# MasterBetaKit-v2-simple.net
KiCad netlist of a schematic drawn in EAGLE
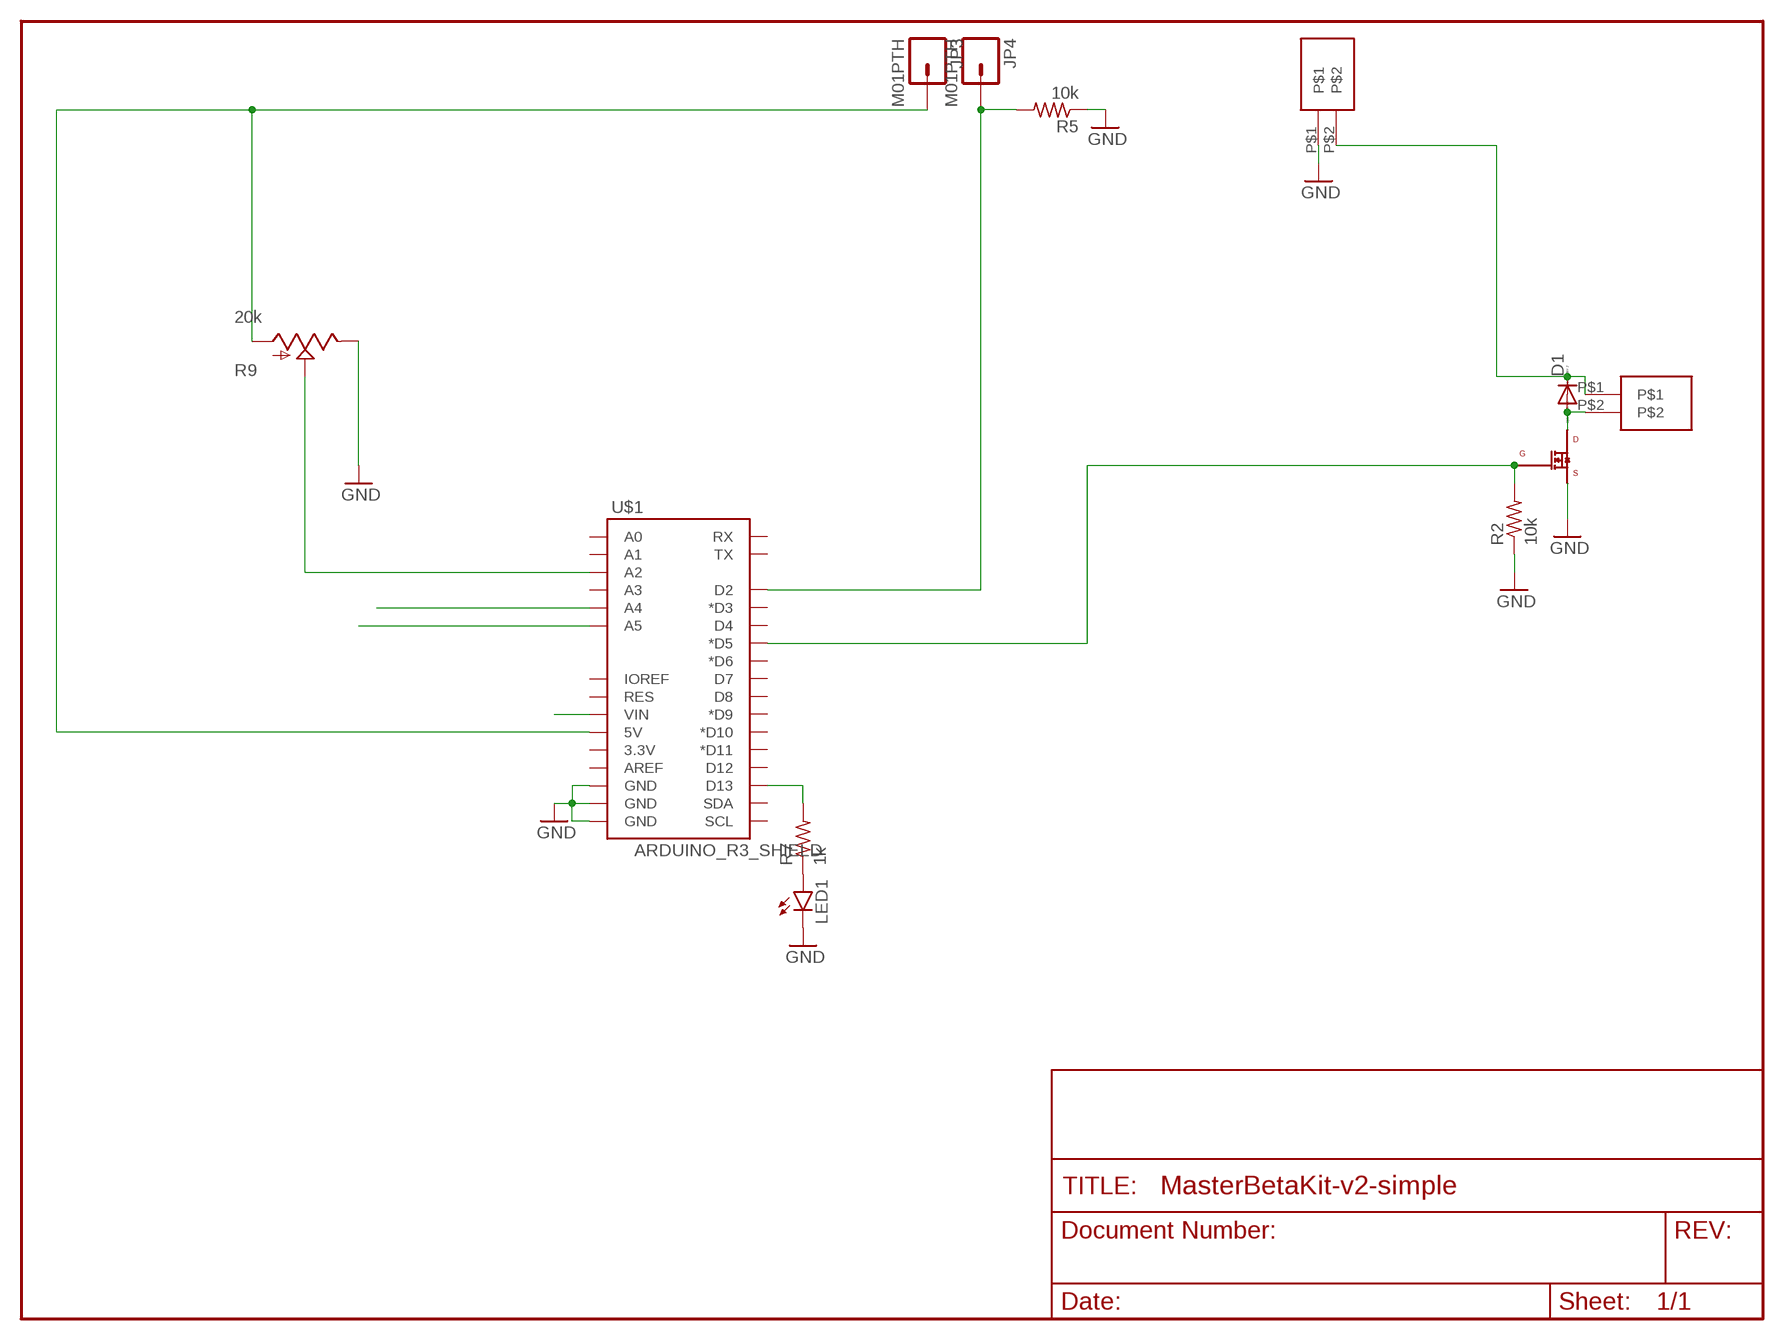
[diagram p0: schematic, sheet 1]

(export (version "E")
  (design (tool "Eeschema 10.0.6"))
  (components
    (comp (ref "D1")
      (value "DIODE-DO-214AC")
      (footprint "eagle-import:DO-214AC")
      (libsource (lib "eagle-import") (part "DIODE-DO-214AC"))
    )
    (comp (ref "JP3")
      (value "M01PTH")
      (footprint "eagle-import:1X01")
      (libsource (lib "eagle-import") (part "M01PTH"))
    )
    (comp (ref "JP4")
      (value "M01PTH")
      (footprint "eagle-import:1X01")
      (libsource (lib "eagle-import") (part "M01PTH"))
    )
    (comp (ref "LED1")
      (value "LED-3MM-NO_SILK")
      (footprint "eagle-import:LED3MM-NS")
      (libsource (lib "eagle-import") (part "LED-3MM-NO_SILK"))
    )
    (comp (ref "R2")
      (value "10k")
      (footprint "eagle-import:R0603")
      (libsource (lib "eagle-import") (part "R-US_R0603"))
    )
    (comp (ref "R5")
      (value "10k")
      (footprint "eagle-import:R0603")
      (libsource (lib "eagle-import") (part "R-US_R0603"))
    )
    (comp (ref "R7")
      (value "1k")
      (footprint "eagle-import:R0603")
      (libsource (lib "eagle-import") (part "R-US_R0603"))
    )
    (comp (ref "R9")
      (value "20k")
      (footprint "eagle-import:ALPS_POT_KIT")
      (libsource (lib "eagle-import") (part "POTALPS-KIT"))
    )
    (comp (ref "U$1")
      (value "ARDUINO_R3_SHIELD")
      (footprint "eagle-import:UNO_R3_SHIELD")
      (libsource (lib "eagle-import") (part "ARDUINO_R3_SHIELD"))
    )
    (comp (ref "U$2")
      (value "IRLML0060")
      (footprint "eagle-import:SOT-23")
      (libsource (lib "eagle-import") (part "IRLML0060"))
    )
    (comp (ref "U$6")
      (value "SPRING-TERMINAL")
      (footprint "eagle-import:SPRING-TERMINAL")
      (libsource (lib "eagle-import") (part "SPRING-TERMINAL"))
    )
    (comp (ref "X3")
      (value "SPRING-TERMINAL")
      (footprint "eagle-import:SPRING-TERMINAL")
      (libsource (lib "eagle-import") (part "SPRING-TERMINAL"))
    )
  )
  (nets
    (net (code "1") (name "GND") (class "Default")
      (node (ref "LED1") (pin "K") (pinfunction "C_K") (pintype "passive"))
      (node (ref "R2") (pin "1") (pinfunction "1_1") (pintype "passive"))
      (node (ref "R5") (pin "1") (pinfunction "1_1") (pintype "passive"))
      (node (ref "R9") (pin "P$1") (pinfunction "E_P$1") (pintype "passive"))
      (node (ref "U$1") (pin "GND@0") (pinfunction "GND_GND@0") (pintype "bidirectional"))
      (node (ref "U$1") (pin "GND@1") (pinfunction "GND_GND@1") (pintype "bidirectional"))
      (node (ref "U$1") (pin "GND@2") (pinfunction "GND_GND@2") (pintype "bidirectional"))
      (node (ref "U$2") (pin "2") (pinfunction "SOURCE_2") (pintype "bidirectional"))
      (node (ref "X3") (pin "P$1") (pinfunction "P$1_P$1") (pintype "bidirectional"))
    )
    (net (code "2") (name "Net-(D1-PadC)") (class "Default")
      (node (ref "D1") (pin "C") (pinfunction "C_C") (pintype "passive"))
      (node (ref "U$6") (pin "P$1") (pinfunction "P$1_P$1") (pintype "bidirectional"))
      (node (ref "X3") (pin "P$2") (pinfunction "P$2_P$2") (pintype "bidirectional"))
    )
    (net (code "3") (name "Net-(JP4-Pad1)") (class "Default")
      (node (ref "JP4") (pin "1") (pinfunction "1_1") (pintype "passive"))
      (node (ref "R5") (pin "2") (pinfunction "2_2") (pintype "passive"))
      (node (ref "U$1") (pin "D2") (pinfunction "D2_D2") (pintype "bidirectional"))
    )
    (net (code "4") (name "Net-(LED1-PadA)") (class "Default")
      (node (ref "LED1") (pin "A") (pinfunction "A_A") (pintype "passive"))
      (node (ref "R7") (pin "1") (pinfunction "1_1") (pintype "passive"))
    )
    (net (code "5") (name "Net-(R7-Pad2)") (class "Default")
      (node (ref "R7") (pin "2") (pinfunction "2_2") (pintype "passive"))
      (node (ref "U$1") (pin "D13") (pinfunction "D13_D13") (pintype "bidirectional"))
    )
    (net (code "6") (name "Net-(R9-A)") (class "Default")
      (node (ref "JP3") (pin "1") (pinfunction "1_1") (pintype "passive"))
      (node (ref "R9") (pin "P$3") (pinfunction "A_P$3") (pintype "passive"))
      (node (ref "U$1") (pin "5V") (pinfunction "5V_5V") (pintype "bidirectional"))
    )
    (net (code "7") (name "Net-(R9-S)") (class "Default")
      (node (ref "R9") (pin "P$2") (pinfunction "S_P$2") (pintype "passive"))
      (node (ref "U$1") (pin "A2") (pinfunction "A2_A2") (pintype "bidirectional"))
    )
    (net (code "8") (name "Net-(U$1-*D5)") (class "Default")
      (node (ref "R2") (pin "2") (pinfunction "2_2") (pintype "passive"))
      (node (ref "U$1") (pin "D5") (pinfunction "*D5_D5") (pintype "bidirectional"))
      (node (ref "U$2") (pin "1") (pinfunction "GATE_1") (pintype "bidirectional"))
    )
    (net (code "9") (name "Net-(U$2-DRAIN)") (class "Default")
      (node (ref "D1") (pin "A") (pinfunction "A_A") (pintype "passive"))
      (node (ref "U$2") (pin "3") (pinfunction "DRAIN_3") (pintype "bidirectional"))
      (node (ref "U$6") (pin "P$2") (pinfunction "P$2_P$2") (pintype "bidirectional"))
    )
    (net (code "10") (name "unconnected-(U$1-*D3-PadD3)") (class "Default")
      (node (ref "U$1") (pin "D3") (pinfunction "*D3_D3") (pintype "bidirectional"))
    )
    (net (code "11") (name "unconnected-(U$1-*D6-PadD6)") (class "Default")
      (node (ref "U$1") (pin "D6") (pinfunction "*D6_D6") (pintype "bidirectional"))
    )
    (net (code "12") (name "unconnected-(U$1-*D9-PadD9)") (class "Default")
      (node (ref "U$1") (pin "D9") (pinfunction "*D9_D9") (pintype "bidirectional"))
    )
    (net (code "13") (name "unconnected-(U$1-*D10-PadD10)") (class "Default")
      (node (ref "U$1") (pin "D10") (pinfunction "*D10_D10") (pintype "bidirectional"))
    )
    (net (code "14") (name "unconnected-(U$1-*D11-PadD11)") (class "Default")
      (node (ref "U$1") (pin "D11") (pinfunction "*D11_D11") (pintype "bidirectional"))
    )
    (net (code "15") (name "unconnected-(U$1-Pad3.3V)") (class "Default")
      (node (ref "U$1") (pin "3.3V") (pinfunction "3.3V_3.3V") (pintype "bidirectional"))
    )
    (net (code "16") (name "unconnected-(U$1-PadA0)") (class "Default")
      (node (ref "U$1") (pin "A0") (pinfunction "A0_A0") (pintype "bidirectional"))
    )
    (net (code "17") (name "unconnected-(U$1-PadA1)") (class "Default")
      (node (ref "U$1") (pin "A1") (pinfunction "A1_A1") (pintype "bidirectional"))
    )
    (net (code "18") (name "unconnected-(U$1-PadA3)") (class "Default")
      (node (ref "U$1") (pin "A3") (pinfunction "A3_A3") (pintype "bidirectional"))
    )
    (net (code "19") (name "unconnected-(U$1-PadA4)") (class "Default")
      (node (ref "U$1") (pin "A4") (pinfunction "A4_A4") (pintype "bidirectional"))
    )
    (net (code "20") (name "unconnected-(U$1-PadA5)") (class "Default")
      (node (ref "U$1") (pin "A5") (pinfunction "A5_A5") (pintype "bidirectional"))
    )
    (net (code "21") (name "unconnected-(U$1-PadAREF)") (class "Default")
      (node (ref "U$1") (pin "AREF") (pinfunction "AREF_AREF") (pintype "bidirectional"))
    )
    (net (code "22") (name "unconnected-(U$1-PadD4)") (class "Default")
      (node (ref "U$1") (pin "D4") (pinfunction "D4_D4") (pintype "bidirectional"))
    )
    (net (code "23") (name "unconnected-(U$1-PadD7)") (class "Default")
      (node (ref "U$1") (pin "D7") (pinfunction "D7_D7") (pintype "bidirectional"))
    )
    (net (code "24") (name "unconnected-(U$1-PadD8)") (class "Default")
      (node (ref "U$1") (pin "D8") (pinfunction "D8_D8") (pintype "bidirectional"))
    )
    (net (code "25") (name "unconnected-(U$1-PadD12)") (class "Default")
      (node (ref "U$1") (pin "D12") (pinfunction "D12_D12") (pintype "bidirectional"))
    )
    (net (code "26") (name "unconnected-(U$1-PadIOREF)") (class "Default")
      (node (ref "U$1") (pin "IOREF") (pinfunction "IOREF_IOREF") (pintype "bidirectional"))
    )
    (net (code "27") (name "unconnected-(U$1-PadRES)") (class "Default")
      (node (ref "U$1") (pin "RES") (pinfunction "RES_RES") (pintype "bidirectional"))
    )
    (net (code "28") (name "unconnected-(U$1-PadRX)") (class "Default")
      (node (ref "U$1") (pin "RX") (pinfunction "RX_RX") (pintype "bidirectional"))
    )
    (net (code "29") (name "unconnected-(U$1-PadSCL)") (class "Default")
      (node (ref "U$1") (pin "SCL") (pinfunction "SCL_SCL") (pintype "bidirectional"))
    )
    (net (code "30") (name "unconnected-(U$1-PadSDA)") (class "Default")
      (node (ref "U$1") (pin "SDA") (pinfunction "SDA_SDA") (pintype "bidirectional"))
    )
    (net (code "31") (name "unconnected-(U$1-PadTX)") (class "Default")
      (node (ref "U$1") (pin "TX") (pinfunction "TX_TX") (pintype "bidirectional"))
    )
    (net (code "32") (name "unconnected-(U$1-PadVIN)") (class "Default")
      (node (ref "U$1") (pin "VIN") (pinfunction "VIN_VIN") (pintype "bidirectional"))
    )
  )
)
